# HWProgUSB.net
KiCad netlist of a schematic drawn in EAGLE
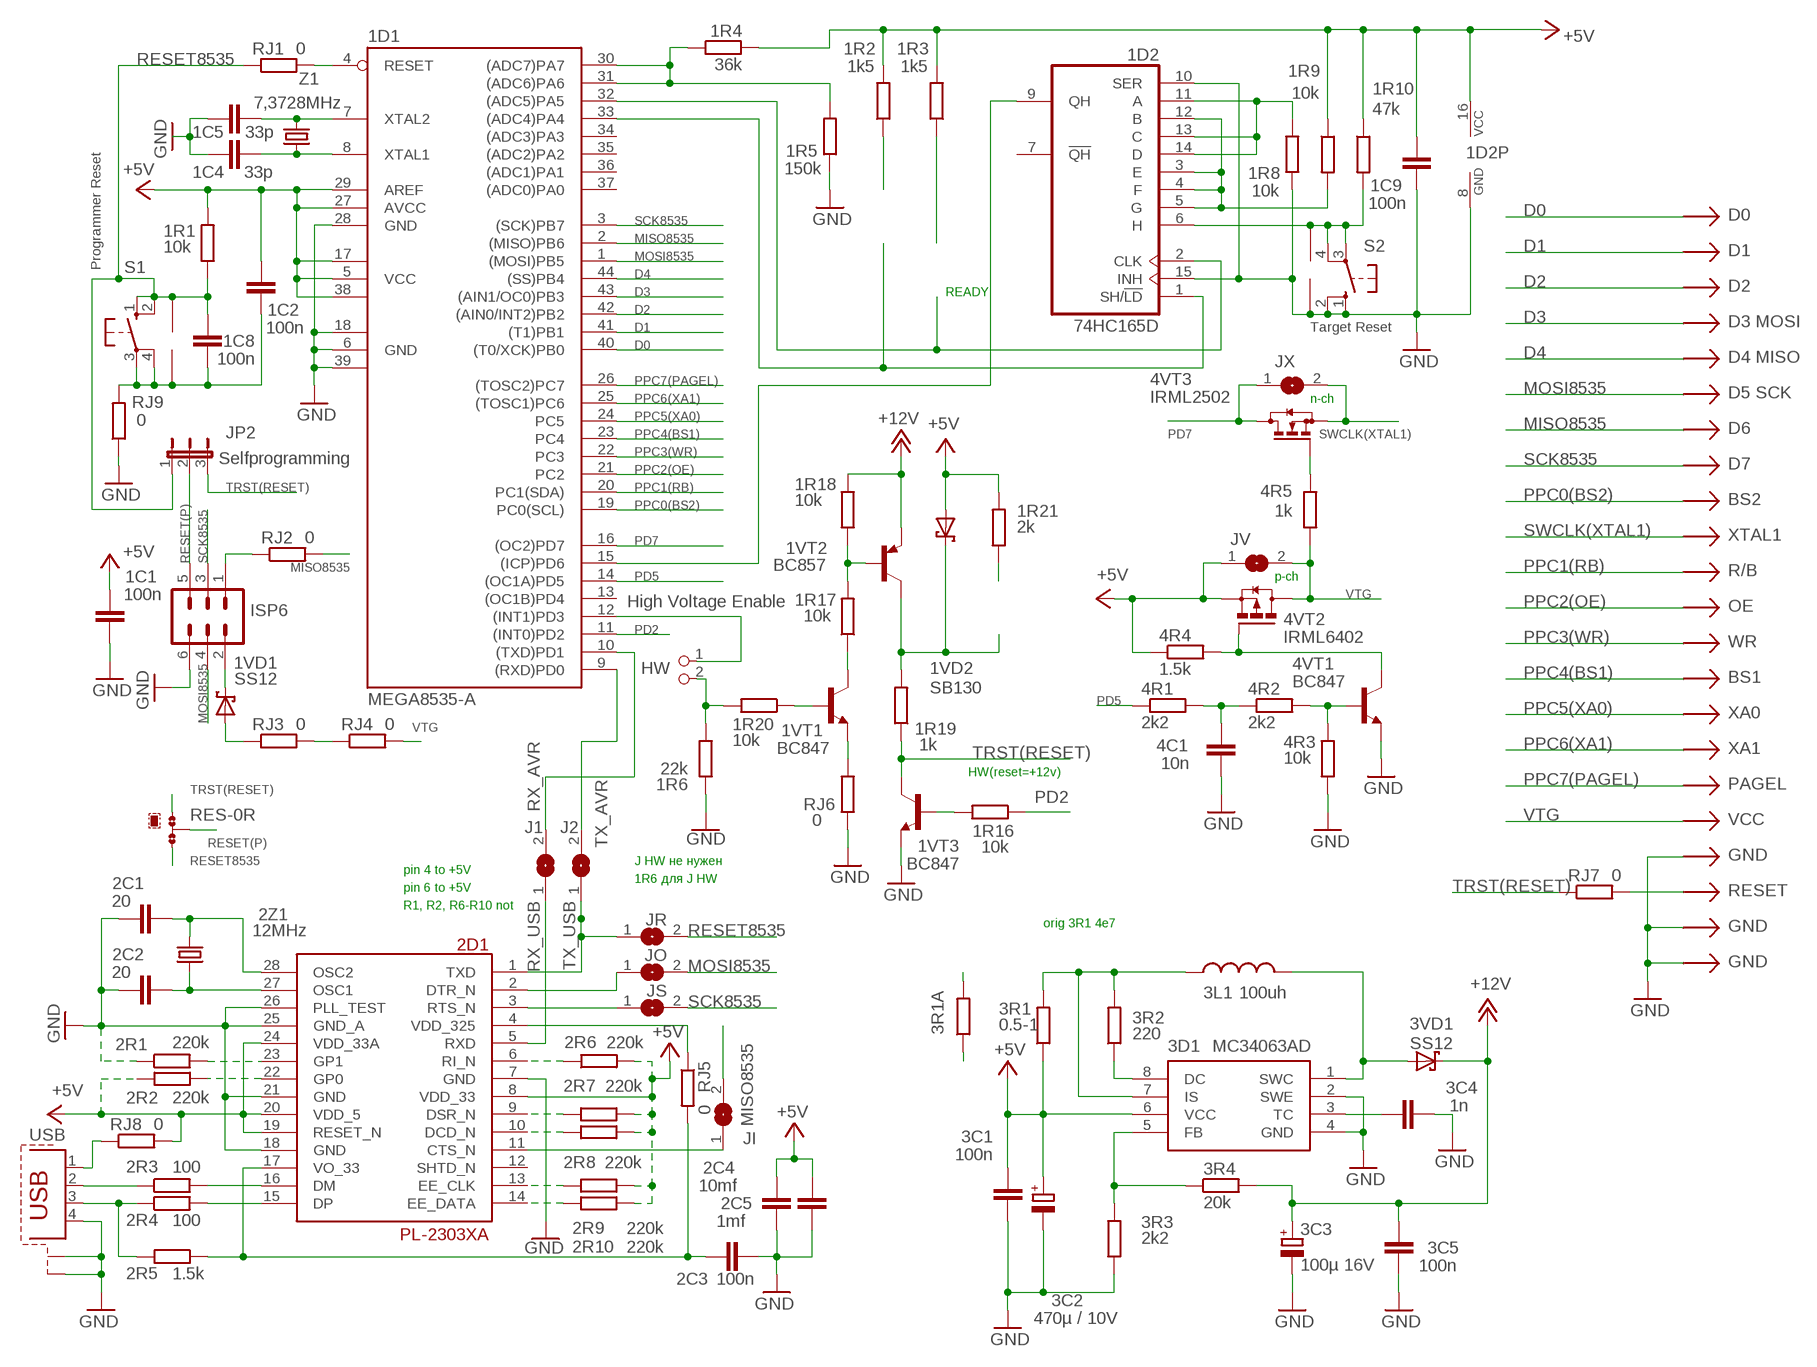
[diagram p0: schematic, sheet 1]

(export (version "E")
  (design (tool "Eeschema 10.0.6"))
  (components
    (comp (ref "1C1")
      (value "100n")
      (footprint "eagle-import:C0805")
      (libsource (lib "eagle-import") (part "rcl_C-EUC0805"))
    )
    (comp (ref "1C2")
      (value "100n")
      (footprint "eagle-import:C0805")
      (libsource (lib "eagle-import") (part "rcl_C-EUC0805"))
    )
    (comp (ref "1C4")
      (value "33p")
      (footprint "eagle-import:C0805")
      (libsource (lib "eagle-import") (part "rcl_C-EUC0805"))
    )
    (comp (ref "1C5")
      (value "33p")
      (footprint "eagle-import:C0805")
      (libsource (lib "eagle-import") (part "rcl_C-EUC0805"))
    )
    (comp (ref "1C8")
      (value "100n")
      (footprint "eagle-import:C0805")
      (libsource (lib "eagle-import") (part "rcl_C-EUC0805"))
    )
    (comp (ref "1C9")
      (value "100n")
      (footprint "eagle-import:C0805")
      (libsource (lib "eagle-import") (part "rcl_C-EUC0805"))
    )
    (comp (ref "1D1")
      (value "MEGA8535-A")
      (footprint "eagle-import:TQFP44")
      (fields (field (name "MPN") "ATMEGA8535-16AU"))
      (libsource (lib "eagle-import") (part "MEGA8535-A"))
    )
    (comp (ref "1D2")
      (value "74HC165D")
      (footprint "eagle-import:SO16")
      (libsource (lib "eagle-import") (part "74165DHC"))
    )
    (comp (ref "1R1")
      (value "10k")
      (footprint "eagle-import:M0805")
      (libsource (lib "eagle-import") (part "R-EU_M0805"))
    )
    (comp (ref "1R2")
      (value "1k5")
      (footprint "eagle-import:M0805")
      (libsource (lib "eagle-import") (part "R-EU_M0805"))
    )
    (comp (ref "1R3")
      (value "1k5")
      (footprint "eagle-import:M0805")
      (libsource (lib "eagle-import") (part "R-EU_M0805"))
    )
    (comp (ref "1R4")
      (value "36k")
      (footprint "eagle-import:M0805")
      (libsource (lib "eagle-import") (part "R-EU_M0805"))
    )
    (comp (ref "1R5")
      (value "150k")
      (footprint "eagle-import:R1206")
      (libsource (lib "eagle-import") (part "R-EU_R1206"))
    )
    (comp (ref "1R6")
      (value "22k")
      (footprint "eagle-import:M1206")
      (libsource (lib "eagle-import") (part "R-EU_M1206"))
    )
    (comp (ref "1R8")
      (value "10k")
      (footprint "eagle-import:M0805")
      (libsource (lib "eagle-import") (part "R-EU_M0805"))
    )
    (comp (ref "1R9")
      (value "10k")
      (footprint "eagle-import:M0805")
      (libsource (lib "eagle-import") (part "R-EU_M0805"))
    )
    (comp (ref "1R10")
      (value "47k")
      (footprint "eagle-import:M0805")
      (libsource (lib "eagle-import") (part "R-EU_M0805"))
    )
    (comp (ref "1R16")
      (value "10k")
      (footprint "eagle-import:R0805")
      (libsource (lib "eagle-import") (part "R-EU_R0805"))
    )
    (comp (ref "1R17")
      (value "10k")
      (footprint "eagle-import:M0805")
      (libsource (lib "eagle-import") (part "R-EU_M0805"))
    )
    (comp (ref "1R18")
      (value "10k")
      (footprint "eagle-import:M0805")
      (libsource (lib "eagle-import") (part "R-EU_M0805"))
    )
    (comp (ref "1R19")
      (value "1k")
      (footprint "eagle-import:M0805")
      (libsource (lib "eagle-import") (part "R-EU_M0805"))
    )
    (comp (ref "1R20")
      (value "10k")
      (footprint "eagle-import:M0805")
      (libsource (lib "eagle-import") (part "R-EU_M0805"))
    )
    (comp (ref "1R21")
      (value "2k")
      (footprint "eagle-import:R1206W")
      (libsource (lib "eagle-import") (part "R-EU_R1206W"))
    )
    (comp (ref "1VD1")
      (value "SS12")
      (footprint "eagle-import:SMB")
      (libsource (lib "eagle-import") (part "SCHOTTKY-DIODESMD"))
    )
    (comp (ref "1VD2")
      (value "SB130")
      (footprint "eagle-import:SMB")
      (libsource (lib "eagle-import") (part "SCHOTTKY-DIODESMD"))
    )
    (comp (ref "1VT1")
      (value "BC847")
      (footprint "eagle-import:SOT23")
      (libsource (lib "eagle-import") (part "BC847"))
    )
    (comp (ref "1VT2")
      (value "BC857")
      (footprint "eagle-import:SOT23-BEC")
      (libsource (lib "eagle-import") (part "-PNP-SOT23-BECBC857A"))
    )
    (comp (ref "1VT3")
      (value "BC847")
      (footprint "eagle-import:SOT23")
      (libsource (lib "eagle-import") (part "BC847"))
    )
    (comp (ref "2C1")
      (value "20")
      (footprint "eagle-import:C0805")
      (libsource (lib "eagle-import") (part "resistor_C-EUC0805"))
    )
    (comp (ref "2C2")
      (value "20")
      (footprint "eagle-import:C0805")
      (libsource (lib "eagle-import") (part "resistor_C-EUC0805"))
    )
    (comp (ref "2C3")
      (value "100n")
      (footprint "eagle-import:C0805")
      (libsource (lib "eagle-import") (part "resistor_C-EUC0805"))
    )
    (comp (ref "2C4")
      (value "10mf")
      (footprint "eagle-import:C1210")
      (libsource (lib "eagle-import") (part "rcl_C-EUC1210"))
    )
    (comp (ref "2C5")
      (value "1mf")
      (footprint "eagle-import:C0805")
      (libsource (lib "eagle-import") (part "rcl_C-EUC0805"))
    )
    (comp (ref "2D1")
      (value "PL-2303XA")
      (footprint "eagle-import:SSOP28DB")
      (libsource (lib "eagle-import") (part "PL-2303XA"))
    )
    (comp (ref "2R1")
      (value "220k")
      (footprint "eagle-import:R0603")
      (libsource (lib "eagle-import") (part "resistor_R-EU_R0603"))
    )
    (comp (ref "2R2")
      (value "220k")
      (footprint "eagle-import:R1206W")
      (libsource (lib "eagle-import") (part "resistor_R-EU_R1206W"))
    )
    (comp (ref "2R3")
      (value "100")
      (footprint "eagle-import:R0603")
      (libsource (lib "eagle-import") (part "resistor_R-EU_R0603"))
    )
    (comp (ref "2R4")
      (value "100")
      (footprint "eagle-import:R0603")
      (libsource (lib "eagle-import") (part "resistor_R-EU_R0603"))
    )
    (comp (ref "2R5")
      (value "1.5k")
      (footprint "eagle-import:R0603")
      (libsource (lib "eagle-import") (part "resistor_R-EU_R0603"))
    )
    (comp (ref "2R6")
      (value "220k")
      (footprint "eagle-import:R1206W")
      (libsource (lib "eagle-import") (part "resistor_R-EU_R1206W"))
    )
    (comp (ref "2R7")
      (value "220k")
      (footprint "eagle-import:R0603")
      (libsource (lib "eagle-import") (part "resistor_R-EU_R0603"))
    )
    (comp (ref "2R8")
      (value "220k")
      (footprint "eagle-import:R0603")
      (libsource (lib "eagle-import") (part "resistor_R-EU_R0603"))
    )
    (comp (ref "2R9")
      (value "220k")
      (footprint "eagle-import:R0603")
      (libsource (lib "eagle-import") (part "resistor_R-EU_R0603"))
    )
    (comp (ref "2R10")
      (value "220k")
      (footprint "eagle-import:R0603")
      (libsource (lib "eagle-import") (part "resistor_R-EU_R0603"))
    )
    (comp (ref "2Z1")
      (value "12MHz")
      (footprint "eagle-import:HC49_S")
      (libsource (lib "eagle-import") (part "CRYSTALHC49S"))
    )
    (comp (ref "3C1")
      (value "100n")
      (footprint "eagle-import:C025-024X044")
      (libsource (lib "eagle-import") (part "C-EU025-024X044"))
    )
    (comp (ref "3C2")
      (value "470µ / 10V")
      (footprint "eagle-import:RCL_E3,5-8")
      (libsource (lib "eagle-import") (part "RCL_CPOL-EUE3.5-8"))
    )
    (comp (ref "3C3")
      (value "100µ 16V")
      (footprint "eagle-import:RCL_E3,5-8")
      (libsource (lib "eagle-import") (part "RCL_CPOL-EUE3.5-8"))
    )
    (comp (ref "3C4")
      (value "1n")
      (footprint "eagle-import:C025-025X050")
      (libsource (lib "eagle-import") (part "rcl_C-EU025-025X050"))
    )
    (comp (ref "3C5")
      (value "100n")
      (footprint "eagle-import:C025-025X050")
      (libsource (lib "eagle-import") (part "rcl_C-EU025-025X050"))
    )
    (comp (ref "3D1")
      (value "MC34063AD")
      (footprint "eagle-import:SOIC8")
      (libsource (lib "eagle-import") (part "MC34063AD"))
    )
    (comp (ref "3L1")
      (value "100uh")
      (footprint "eagle-import:0207_10")
      (libsource (lib "eagle-import") (part "L-US0207/10"))
    )
    (comp (ref "3R1")
      (value "0.5-1")
      (footprint "eagle-import:0204_7")
      (libsource (lib "eagle-import") (part "R-EU_0204/7"))
    )
    (comp (ref "3R1A")
      (value "R-EU_0204/7")
      (footprint "eagle-import:0204_7")
      (libsource (lib "eagle-import") (part "R-EU_0204/7"))
    )
    (comp (ref "3R2")
      (value "220")
      (footprint "eagle-import:0204_7")
      (libsource (lib "eagle-import") (part "R-EU_0204/7"))
    )
    (comp (ref "3R3")
      (value "2k2")
      (footprint "eagle-import:M0805")
      (libsource (lib "eagle-import") (part "R-EU_M0805"))
    )
    (comp (ref "3R4")
      (value "20k")
      (footprint "eagle-import:M0805")
      (libsource (lib "eagle-import") (part "R-EU_M0805"))
    )
    (comp (ref "3VD1")
      (value "SS12")
      (footprint "eagle-import:SMB")
      (libsource (lib "eagle-import") (part "SCHOTTKY-DIODESMD"))
    )
    (comp (ref "4C1")
      (value "10n")
      (footprint "eagle-import:C1206")
      (libsource (lib "eagle-import") (part "rcl_C-EUC1206"))
    )
    (comp (ref "4R1")
      (value "2k2")
      (footprint "eagle-import:M0805")
      (libsource (lib "eagle-import") (part "R-EU_M0805"))
    )
    (comp (ref "4R2")
      (value "2k2")
      (footprint "eagle-import:M1206")
      (libsource (lib "eagle-import") (part "R-EU_M1206"))
    )
    (comp (ref "4R3")
      (value "10k")
      (footprint "eagle-import:M0805")
      (libsource (lib "eagle-import") (part "R-EU_M0805"))
    )
    (comp (ref "4R4")
      (value "1.5k")
      (footprint "eagle-import:M0805")
      (libsource (lib "eagle-import") (part "R-EU_M0805"))
    )
    (comp (ref "4R5")
      (value "1k")
      (footprint "eagle-import:M0805")
      (libsource (lib "eagle-import") (part "R-EU_M0805"))
    )
    (comp (ref "4VT1")
      (value "BC847")
      (footprint "eagle-import:SOT23")
      (libsource (lib "eagle-import") (part "transistor-neu-to92_BC847"))
    )
    (comp (ref "4VT2")
      (value "IRML6402")
      (footprint "eagle-import:SUPER-SOT3")
      (libsource (lib "eagle-import") (part "FDN360P"))
    )
    (comp (ref "4VT3")
      (value "IRML2502")
      (footprint "eagle-import:SOT23")
      (libsource (lib "eagle-import") (part "BSS123"))
    )
    (comp (ref "HW")
      (value "High Voltage Enable")
      (footprint "eagle-import:PINHEAD_1X02")
      (libsource (lib "eagle-import") (part "PINHEAD_PINHD-1X2"))
    )
    (comp (ref "ISP6")
      (value "MA03-2")
      (footprint "eagle-import:MA03-2")
      (libsource (lib "eagle-import") (part "MA03-2"))
    )
    (comp (ref "J1") (value "SJ") (footprint "eagle-import:SJ") (libsource (lib "eagle-import") (part "SJ")))
    (comp (ref "J2") (value "SJ") (footprint "eagle-import:SJ") (libsource (lib "eagle-import") (part "SJ")))
    (comp (ref "JI") (value "SJ") (footprint "eagle-import:SJ") (libsource (lib "eagle-import") (part "SJ")))
    (comp (ref "JO") (value "SJ") (footprint "eagle-import:SJ") (libsource (lib "eagle-import") (part "SJ")))
    (comp (ref "JP2")
      (value "Selfprogramming")
      (footprint "eagle-import:JUMPER_JP2")
      (libsource (lib "eagle-import") (part "JUMPER_JP2E"))
    )
    (comp (ref "JR") (value "SJ") (footprint "eagle-import:SJ") (libsource (lib "eagle-import") (part "SJ")))
    (comp (ref "JS") (value "SJ") (footprint "eagle-import:SJ") (libsource (lib "eagle-import") (part "SJ")))
    (comp (ref "JV") (value "SJ") (footprint "eagle-import:SJ") (libsource (lib "eagle-import") (part "SJ")))
    (comp (ref "JX") (value "SJ") (footprint "eagle-import:SJ") (libsource (lib "eagle-import") (part "SJ")))
    (comp (ref "RES")
      (value "0R-JUMPA")
      (footprint "eagle-import:A0R-JMP")
      (libsource (lib "eagle-import") (part "0R-JUMPA"))
    )
    (comp (ref "RJ1")
      (value "0")
      (footprint "eagle-import:R1206")
      (libsource (lib "eagle-import") (part "R-EU_R1206"))
    )
    (comp (ref "RJ2")
      (value "0")
      (footprint "eagle-import:R1206")
      (libsource (lib "eagle-import") (part "R-EU_R1206"))
    )
    (comp (ref "RJ3")
      (value "0")
      (footprint "eagle-import:R1206")
      (libsource (lib "eagle-import") (part "R-EU_R1206"))
    )
    (comp (ref "RJ4")
      (value "0")
      (footprint "eagle-import:R1206")
      (libsource (lib "eagle-import") (part "R-EU_R1206"))
    )
    (comp (ref "RJ5")
      (value "0")
      (footprint "eagle-import:R1206")
      (libsource (lib "eagle-import") (part "R-EU_R1206"))
    )
    (comp (ref "RJ6")
      (value "0")
      (footprint "eagle-import:R1206")
      (libsource (lib "eagle-import") (part "R-EU_R1206"))
    )
    (comp (ref "RJ7")
      (value "0")
      (footprint "eagle-import:R1206")
      (libsource (lib "eagle-import") (part "R-EU_R1206"))
    )
    (comp (ref "RJ8")
      (value "0")
      (footprint "eagle-import:R1206")
      (libsource (lib "eagle-import") (part "R-EU_R1206"))
    )
    (comp (ref "RJ9")
      (value "0")
      (footprint "eagle-import:R1206")
      (libsource (lib "eagle-import") (part "R-EU_R1206"))
    )
    (comp (ref "S1")
      (value "10-XX")
      (footprint "eagle-import:B3F-10XX")
      (libsource (lib "eagle-import") (part "10-XX"))
    )
    (comp (ref "S2")
      (value "10-XX")
      (footprint "eagle-import:B3F-10XX")
      (libsource (lib "eagle-import") (part "10-XX"))
    )
    (comp (ref "U$1")
      (value "5.08")
      (footprint "eagle-import:KEY")
      (libsource (lib "eagle-import") (part "5.08"))
    )
    (comp (ref "U$2")
      (value "5.08")
      (footprint "eagle-import:KEY")
      (libsource (lib "eagle-import") (part "5.08"))
    )
    (comp (ref "USB")
      (value "PROGRAMMER_PN61729-S")
      (footprint "eagle-import:PROGRAMMER_PN61729-S")
      (libsource (lib "eagle-import") (part "PROGRAMMER_PN61729-S"))
    )
    (comp (ref "X2")
      (value "P_AVR_P")
      (footprint "eagle-import:P_AVR")
      (libsource (lib "eagle-import") (part "P_AVR_P"))
    )
    (comp (ref "Z1")
      (value "7,3728MHz")
      (footprint "eagle-import:HC49U-V")
      (libsource (lib "eagle-import") (part "CRYTALHC49U-V"))
    )
  )
  (nets
    (net (code "1") (name "+5V") (class "Default")
      (node (ref "1C1") (pin "2") (pinfunction "2_2") (pintype "passive"))
      (node (ref "1C2") (pin "2") (pinfunction "2_2") (pintype "passive"))
      (node (ref "1C9") (pin "1") (pinfunction "1_1") (pintype "passive"))
      (node (ref "1D1") (pin "17") (pinfunction "VCC1_17") (pintype "power_in"))
      (node (ref "1D1") (pin "27") (pinfunction "AVCC_27") (pintype "power_in"))
      (node (ref "1D1") (pin "29") (pinfunction "AREF_29") (pintype "passive"))
      (node (ref "1D1") (pin "38") (pinfunction "VCC2_38") (pintype "power_in"))
      (node (ref "1D1") (pin "5") (pinfunction "VCC_5") (pintype "power_in"))
      (node (ref "1D2") (pin "16") (pinfunction "VCC_16") (pintype "power_in"))
      (node (ref "1R1") (pin "2") (pinfunction "2_2") (pintype "passive"))
      (node (ref "1R10") (pin "1") (pinfunction "1_1") (pintype "passive"))
      (node (ref "1R2") (pin "2") (pinfunction "2_2") (pintype "passive"))
      (node (ref "1R21") (pin "2") (pinfunction "2_2") (pintype "passive"))
      (node (ref "1R3") (pin "2") (pinfunction "2_2") (pintype "passive"))
      (node (ref "1R4") (pin "2") (pinfunction "2_2") (pintype "passive"))
      (node (ref "1R9") (pin "1") (pinfunction "1_1") (pintype "passive"))
      (node (ref "1VD2") (pin "A") (pinfunction "A_A") (pintype "passive"))
      (node (ref "2C4") (pin "2") (pinfunction "2_2") (pintype "passive"))
      (node (ref "2C5") (pin "2") (pinfunction "2_2") (pintype "passive"))
      (node (ref "2D1") (pin "19") (pinfunction "RESET_N_19") (pintype "bidirectional"))
      (node (ref "2D1") (pin "20") (pinfunction "VDD_5_20") (pintype "bidirectional"))
      (node (ref "2D1") (pin "24") (pinfunction "VDD_33A_24") (pintype "bidirectional"))
      (node (ref "2D1") (pin "8") (pinfunction "VDD_33_8") (pintype "bidirectional"))
      (node (ref "2R10") (pin "1") (pinfunction "1_1") (pintype "passive"))
      (node (ref "2R2") (pin "1") (pinfunction "1_1") (pintype "passive"))
      (node (ref "2R6") (pin "2") (pinfunction "2_2") (pintype "passive"))
      (node (ref "2R7") (pin "1") (pinfunction "1_1") (pintype "passive"))
      (node (ref "2R8") (pin "1") (pinfunction "1_1") (pintype "passive"))
      (node (ref "2R9") (pin "1") (pinfunction "1_1") (pintype "passive"))
      (node (ref "3C1") (pin "1") (pinfunction "1_1") (pintype "passive"))
      (node (ref "3C2") (pin "+") (pinfunction "+_+") (pintype "passive"))
      (node (ref "3D1") (pin "6") (pinfunction "VCC_6") (pintype "passive"))
      (node (ref "3R1") (pin "1") (pinfunction "1_1") (pintype "passive"))
      (node (ref "3R1A") (pin "1") (pinfunction "1_1") (pintype "passive"))
      (node (ref "4R4") (pin "1") (pinfunction "1_1") (pintype "passive"))
      (node (ref "4VT2") (pin "2") (pinfunction "S_2") (pintype "passive"))
      (node (ref "JV") (pin "1") (pinfunction "1_1") (pintype "passive"))
      (node (ref "RJ8") (pin "2") (pinfunction "2_2") (pintype "passive"))
    )
    (net (code "2") (name "+12V") (class "Default")
      (node (ref "1R18") (pin "2") (pinfunction "2_2") (pintype "passive"))
      (node (ref "1VT2") (pin "E") (pinfunction "E_E") (pintype "passive"))
      (node (ref "3C3") (pin "+") (pinfunction "+_+") (pintype "passive"))
      (node (ref "3C5") (pin "2") (pinfunction "2_2") (pintype "passive"))
      (node (ref "3R4") (pin "2") (pinfunction "2_2") (pintype "passive"))
      (node (ref "3VD1") (pin "C") (pinfunction "C_C") (pintype "passive"))
    )
    (net (code "3") (name "/D0") (class "Default")
      (node (ref "1D1") (pin "40") (pinfunction "(T0/XCK)PB0_40") (pintype "bidirectional"))
      (node (ref "X2") (pin "D0") (pinfunction "D0_D0") (pintype "bidirectional"))
    )
    (net (code "4") (name "/D1") (class "Default")
      (node (ref "1D1") (pin "41") (pinfunction "(T1)PB1_41") (pintype "bidirectional"))
      (node (ref "X2") (pin "D1") (pinfunction "D1_D1") (pintype "bidirectional"))
    )
    (net (code "5") (name "/D2") (class "Default")
      (node (ref "1D1") (pin "42") (pinfunction "(AIN0/INT2)PB2_42") (pintype "bidirectional"))
      (node (ref "X2") (pin "D2") (pinfunction "D2_D2") (pintype "bidirectional"))
    )
    (net (code "6") (name "/D3") (class "Default")
      (node (ref "1D1") (pin "43") (pinfunction "(AIN1/OC0)PB3_43") (pintype "bidirectional"))
      (node (ref "X2") (pin "D3") (pinfunction "D3_D3") (pintype "bidirectional"))
    )
    (net (code "7") (name "/D4") (class "Default")
      (node (ref "1D1") (pin "44") (pinfunction "(SS)PB4_44") (pintype "bidirectional"))
      (node (ref "X2") (pin "D4") (pinfunction "D4_D4") (pintype "bidirectional"))
    )
    (net (code "8") (name "/MISO8535") (class "Default")
      (node (ref "1D1") (pin "2") (pinfunction "(MISO)PB6_2") (pintype "bidirectional"))
      (node (ref "JI") (pin "2") (pinfunction "2_2") (pintype "passive"))
      (node (ref "RJ2") (pin "2") (pinfunction "2_2") (pintype "passive"))
      (node (ref "X2") (pin "D6") (pinfunction "D6_D6") (pintype "bidirectional"))
    )
    (net (code "9") (name "/MOSI8535") (class "Default")
      (node (ref "1D1") (pin "1") (pinfunction "(MOSI)PB5_1") (pintype "bidirectional"))
      (node (ref "ISP6") (pin "4") (pinfunction "4_4") (pintype "passive"))
      (node (ref "JO") (pin "2") (pinfunction "2_2") (pintype "passive"))
      (node (ref "X2") (pin "D5") (pinfunction "D5_D5") (pintype "bidirectional"))
    )
    (net (code "10") (name "/N$105") (class "Default")
      (node (ref "3D1") (pin "7") (pinfunction "IS_7") (pintype "passive"))
      (node (ref "3L1") (pin "1") (pinfunction "1_1") (pintype "passive"))
      (node (ref "3R1") (pin "2") (pinfunction "2_2") (pintype "passive"))
      (node (ref "3R1A") (pin "2") (pinfunction "2_2") (pintype "passive"))
      (node (ref "3R2") (pin "2") (pinfunction "2_2") (pintype "passive"))
    )
    (net (code "11") (name "/PD2") (class "Default")
      (node (ref "1D1") (pin "11") (pinfunction "(INT0)PD2_11") (pintype "bidirectional"))
      (node (ref "1R16") (pin "1") (pinfunction "1_1") (pintype "passive"))
    )
    (net (code "12") (name "/PD5") (class "Default")
      (node (ref "1D1") (pin "14") (pinfunction "(OC1A)PD5_14") (pintype "bidirectional"))
      (node (ref "4R1") (pin "1") (pinfunction "1_1") (pintype "passive"))
    )
    (net (code "13") (name "/PD7") (class "Default")
      (node (ref "1D1") (pin "16") (pinfunction "(OC2)PD7_16") (pintype "bidirectional"))
      (node (ref "4VT3") (pin "3") (pinfunction "D_3") (pintype "passive"))
      (node (ref "JX") (pin "1") (pinfunction "1_1") (pintype "passive"))
    )
    (net (code "14") (name "/PPC0(BS2)") (class "Default")
      (node (ref "1D1") (pin "19") (pinfunction "PC0(SCL)_19") (pintype "bidirectional"))
      (node (ref "X2") (pin "BS2") (pinfunction "BS2_BS2") (pintype "bidirectional"))
    )
    (net (code "15") (name "/PPC1(RB)") (class "Default")
      (node (ref "1D1") (pin "20") (pinfunction "PC1(SDA)_20") (pintype "bidirectional"))
      (node (ref "X2") (pin "RB") (pinfunction "RB_RB") (pintype "bidirectional"))
    )
    (net (code "16") (name "/PPC2(OE)") (class "Default")
      (node (ref "1D1") (pin "21") (pinfunction "PC2_21") (pintype "bidirectional"))
      (node (ref "X2") (pin "OE") (pinfunction "OE_OE") (pintype "bidirectional"))
    )
    (net (code "17") (name "/PPC3(WR)") (class "Default")
      (node (ref "1D1") (pin "22") (pinfunction "PC3_22") (pintype "bidirectional"))
      (node (ref "X2") (pin "WR") (pinfunction "WR_WR") (pintype "bidirectional"))
    )
    (net (code "18") (name "/PPC4(BS1)") (class "Default")
      (node (ref "1D1") (pin "23") (pinfunction "PC4_23") (pintype "bidirectional"))
      (node (ref "X2") (pin "BS1") (pinfunction "BS1_BS1") (pintype "bidirectional"))
    )
    (net (code "19") (name "/PPC5(XA0)") (class "Default")
      (node (ref "1D1") (pin "24") (pinfunction "PC5_24") (pintype "bidirectional"))
      (node (ref "X2") (pin "XA0") (pinfunction "XA0_XA0") (pintype "bidirectional"))
    )
    (net (code "20") (name "/PPC6(XA1)") (class "Default")
      (node (ref "1D1") (pin "25") (pinfunction "(TOSC1)PC6_25") (pintype "bidirectional"))
      (node (ref "X2") (pin "XA1") (pinfunction "XA1_XA1") (pintype "bidirectional"))
    )
    (net (code "21") (name "/PPC7(PAGEL)") (class "Default")
      (node (ref "1D1") (pin "26") (pinfunction "(TOSC2)PC7_26") (pintype "bidirectional"))
      (node (ref "X2") (pin "PAGEL") (pinfunction "PAGEL_PAGEL") (pintype "bidirectional"))
    )
    (net (code "22") (name "/RESET(P)") (class "Default")
      (node (ref "ISP6") (pin "5") (pinfunction "5_5") (pintype "passive"))
      (node (ref "JP2") (pin "2") (pinfunction "2_2") (pintype "passive"))
      (node (ref "RES") (pin "2") (pinfunction "2_2") (pintype "passive"))
    )
    (net (code "23") (name "/RESET8535") (class "Default")
      (node (ref "1C8") (pin "2") (pinfunction "2_2") (pintype "passive"))
      (node (ref "1R1") (pin "1") (pinfunction "1_1") (pintype "passive"))
      (node (ref "JP2") (pin "1") (pinfunction "1_1") (pintype "passive"))
      (node (ref "JR") (pin "2") (pinfunction "2_2") (pintype "passive"))
      (node (ref "RES") (pin "3") (pinfunction "3_3") (pintype "passive"))
      (node (ref "RJ1") (pin "1") (pinfunction "1_1") (pintype "passive"))
      (node (ref "S1") (pin "1") (pinfunction "S_1") (pintype "passive"))
      (node (ref "S1") (pin "2") (pinfunction "S1_2") (pintype "passive"))
      (node (ref "U$1") (pin "P$2") (pinfunction "P$2_P$2") (pintype "bidirectional"))
    )
    (net (code "24") (name "/RX_AVR") (class "Default")
      (node (ref "1D1") (pin "10") (pinfunction "(TXD)PD1_10") (pintype "bidirectional"))
      (node (ref "J1") (pin "2") (pinfunction "2_2") (pintype "passive"))
    )
    (net (code "25") (name "/RX_USB") (class "Default")
      (node (ref "2D1") (pin "5") (pinfunction "RXD_5") (pintype "bidirectional"))
      (node (ref "J1") (pin "1") (pinfunction "1_1") (pintype "passive"))
    )
    (net (code "26") (name "/SCK8535") (class "Default")
      (node (ref "1D1") (pin "3") (pinfunction "(SCK)PB7_3") (pintype "bidirectional"))
      (node (ref "ISP6") (pin "3") (pinfunction "3_3") (pintype "passive"))
      (node (ref "JS") (pin "2") (pinfunction "2_2") (pintype "passive"))
      (node (ref "X2") (pin "D7") (pinfunction "D7_D7") (pintype "bidirectional"))
    )
    (net (code "27") (name "/SWCLK(XTAL1)") (class "Default")
      (node (ref "4VT3") (pin "2") (pinfunction "S_2") (pintype "passive"))
      (node (ref "JX") (pin "2") (pinfunction "2_2") (pintype "passive"))
      (node (ref "X2") (pin "XTAL1") (pinfunction "XTAL1_XTAL1") (pintype "bidirectional"))
    )
    (net (code "28") (name "/TRST(RESET)") (class "Default")
      (node (ref "1R19") (pin "1") (pinfunction "1_1") (pintype "passive"))
      (node (ref "1VT3") (pin "3") (pinfunction "C_3") (pintype "passive"))
      (node (ref "JP2") (pin "3") (pinfunction "3_3") (pintype "passive"))
      (node (ref "RES") (pin "1") (pinfunction "1_1") (pintype "passive"))
      (node (ref "RJ7") (pin "1") (pinfunction "1_1") (pintype "passive"))
    )
    (net (code "29") (name "/TX_AVR") (class "Default")
      (node (ref "1D1") (pin "9") (pinfunction "(RXD)PD0_9") (pintype "bidirectional"))
      (node (ref "J2") (pin "2") (pinfunction "2_2") (pintype "passive"))
    )
    (net (code "30") (name "/TX_USB") (class "Default")
      (node (ref "2D1") (pin "1") (pinfunction "TXD_1") (pintype "bidirectional"))
      (node (ref "J2") (pin "1") (pinfunction "1_1") (pintype "passive"))
      (node (ref "JR") (pin "1") (pinfunction "1_1") (pintype "passive"))
    )
    (net (code "31") (name "/VTG") (class "Default")
      (node (ref "4R5") (pin "1") (pinfunction "1_1") (pintype "passive"))
      (node (ref "4VT2") (pin "3") (pinfunction "D_3") (pintype "passive"))
      (node (ref "JV") (pin "2") (pinfunction "2_2") (pintype "passive"))
      (node (ref "RJ4") (pin "2") (pinfunction "2_2") (pintype "passive"))
      (node (ref "X2") (pin "VCC") (pinfunction "VCC_VCC") (pintype "bidirectional"))
    )
    (net (code "32") (name "GND") (class "Default")
      (node (ref "1C1") (pin "1") (pinfunction "1_1") (pintype "passive"))
      (node (ref "1C4") (pin "1") (pinfunction "1_1") (pintype "passive"))
      (node (ref "1C5") (pin "1") (pinfunction "1_1") (pintype "passive"))
      (node (ref "1C9") (pin "2") (pinfunction "2_2") (pintype "passive"))
      (node (ref "1D1") (pin "18") (pinfunction "GND1_18") (pintype "power_in"))
      (node (ref "1D1") (pin "28") (pinfunction "GND_28") (pintype "power_in"))
      (node (ref "1D1") (pin "39") (pinfunction "GND2_39") (pintype "power_in"))
      (node (ref "1D1") (pin "6") (pinfunction "GND_6") (pintype "power_in"))
      (node (ref "1D2") (pin "10") (pinfunction "SER_10") (pintype "input"))
      (node (ref "1D2") (pin "15") (pinfunction "INH_15") (pintype "input"))
      (node (ref "1D2") (pin "8") (pinfunction "GND_8") (pintype "power_in"))
      (node (ref "1R5") (pin "1") (pinfunction "1_1") (pintype "passive"))
      (node (ref "1R6") (pin "1") (pinfunction "1_1") (pintype "passive"))
      (node (ref "1R8") (pin "1") (pinfunction "1_1") (pintype "passive"))
      (node (ref "1VT3") (pin "2") (pinfunction "E_2") (pintype "passive"))
      (node (ref "2C1") (pin "1") (pinfunction "1_1") (pintype "passive"))
      (node (ref "2C2") (pin "1") (pinfunction "1_1") (pintype "passive"))
      (node (ref "2C3") (pin "2") (pinfunction "2_2") (pintype "passive"))
      (node (ref "2C4") (pin "1") (pinfunction "1_1") (pintype "passive"))
      (node (ref "2C5") (pin "1") (pinfunction "1_1") (pintype "passive"))
      (node (ref "2D1") (pin "18") (pinfunction "GND_18") (pintype "bidirectional"))
      (node (ref "2D1") (pin "21") (pinfunction "GND_21") (pintype "bidirectional"))
      (node (ref "2D1") (pin "25") (pinfunction "GND_A_25") (pintype "bidirectional"))
      (node (ref "2D1") (pin "26") (pinfunction "PLL_TEST_26") (pintype "bidirectional"))
      (node (ref "2D1") (pin "7") (pinfunction "GND_7") (pintype "bidirectional"))
      (node (ref "2R1") (pin "1") (pinfunction "1_1") (pintype "passive"))
      (node (ref "3C1") (pin "2") (pinfunction "2_2") (pintype "passive"))
      (node (ref "3C2") (pin "-") (pinfunction "-_-") (pintype "passive"))
      (node (ref "3C3") (pin "-") (pinfunction "-_-") (pintype "passive"))
      (node (ref "3C4") (pin "2") (pinfunction "2_2") (pintype "passive"))
      (node (ref "3C5") (pin "1") (pinfunction "1_1") (pintype "passive"))
      (node (ref "3D1") (pin "2") (pinfunction "SWE_2") (pintype "passive"))
      (node (ref "3D1") (pin "4") (pinfunction "GND_4") (pintype "passive"))
      (node (ref "3R3") (pin "1") (pinfunction "1_1") (pintype "passive"))
      (node (ref "4C1") (pin "1") (pinfunction "1_1") (pintype "passive"))
      (node (ref "4R3") (pin "1") (pinfunction "1_1") (pintype "passive"))
      (node (ref "4VT1") (pin "2") (pinfunction "E_2") (pintype "passive"))
      (node (ref "ISP6") (pin "6") (pinfunction "6_6") (pintype "passive"))
      (node (ref "RJ6") (pin "1") (pinfunction "1_1") (pintype "passive"))
      (node (ref "RJ9") (pin "1") (pinfunction "1_1") (pintype "passive"))
      (node (ref "S2") (pin "1") (pinfunction "S_1") (pintype "passive"))
      (node (ref "S2") (pin "2") (pinfunction "S1_2") (pintype "passive"))
      (node (ref "U$2") (pin "P$1") (pinfunction "P$1_P$1") (pintype "bidirectional"))
      (node (ref "USB") (pin "4") (pinfunction "4_4") (pintype "passive"))
      (node (ref "USB") (pin "S1") (pinfunction "S1_S1") (pintype "passive"))
      (node (ref "USB") (pin "S2") (pinfunction "S2_S2") (pintype "passive"))
      (node (ref "X2") (pin "GND") (pinfunction "GND_GND") (pintype "bidirectional"))
      (node (ref "X2") (pin "GND2") (pinfunction "GND2_GND2") (pintype "bidirectional"))
      (node (ref "X2") (pin "P$1") (pinfunction "LGND_P$1") (pintype "bidirectional"))
    )
    (net (code "33") (name "Net-(1D1-(ADC4)PA4)") (class "Default")
      (node (ref "1D1") (pin "33") (pinfunction "(ADC4)PA4_33") (pintype "bidirectional"))
      (node (ref "1D2") (pin "1") (pinfunction "SH/~{LD}_1") (pintype "input"))
    )
    (net (code "34") (name "Net-(1D1-(ADC5)PA5)") (class "Default")
      (node (ref "1D1") (pin "32") (pinfunction "(ADC5)PA5_32") (pintype "bidirectional"))
      (node (ref "1D2") (pin "2") (pinfunction "CLK_2") (pintype "input"))
    )
    (net (code "35") (name "Net-(1D1-(ADC6)PA6)") (class "Default")
      (node (ref "1D1") (pin "30") (pinfunction "(ADC7)PA7_30") (pintype "bidirectional"))
      (node (ref "1D1") (pin "31") (pinfunction "(ADC6)PA6_31") (pintype "bidirectional"))
      (node (ref "1R4") (pin "1") (pinfunction "1_1") (pintype "passive"))
      (node (ref "1R5") (pin "2") (pinfunction "2_2") (pintype "passive"))
    )
    (net (code "36") (name "Net-(1D1-(ICP)PD6)") (class "Default")
      (node (ref "1D1") (pin "15") (pinfunction "(ICP)PD6_15") (pintype "bidirectional"))
      (node (ref "1D2") (pin "9") (pinfunction "QH_9") (pintype "output"))
    )
    (net (code "37") (name "Net-(1D1-(INT1)PD3)") (class "Default")
      (node (ref "1D1") (pin "12") (pinfunction "(INT1)PD3_12") (pintype "bidirectional"))
      (node (ref "HW") (pin "1") (pinfunction "1_1") (pintype "passive"))
    )
    (net (code "38") (name "Net-(1D1-RESET)") (class "Default")
      (node (ref "1D1") (pin "4") (pinfunction "RESET_4") (pintype "input"))
      (node (ref "RJ1") (pin "2") (pinfunction "2_2") (pintype "passive"))
    )
    (net (code "39") (name "Net-(1D1-XTAL1)") (class "Default")
      (node (ref "1C4") (pin "2") (pinfunction "2_2") (pintype "passive"))
      (node (ref "1D1") (pin "8") (pinfunction "XTAL1_8") (pintype "bidirectional"))
      (node (ref "Z1") (pin "1") (pinfunction "1_1") (pintype "passive"))
    )
    (net (code "40") (name "Net-(1D1-XTAL2)") (class "Default")
      (node (ref "1C5") (pin "2") (pinfunction "2_2") (pintype "passive"))
      (node (ref "1D1") (pin "7") (pinfunction "XTAL2_7") (pintype "bidirectional"))
      (node (ref "Z1") (pin "2") (pinfunction "2_2") (pintype "passive"))
    )
    (net (code "41") (name "Net-(1D2A-A)") (class "Default")
      (node (ref "1D2") (pin "11") (pinfunction "A_11") (pintype "input"))
      (node (ref "1D2") (pin "13") (pinfunction "C_13") (pintype "input"))
      (node (ref "1D2") (pin "14") (pinfunction "D_14") (pintype "input"))
      (node (ref "1R8") (pin "2") (pinfunction "2_2") (pintype "passive"))
    )
    (net (code "42") (name "Net-(1D2A-B)") (class "Default")
      (node (ref "1D2") (pin "12") (pinfunction "B_12") (pintype "input"))
      (node (ref "1D2") (pin "3") (pinfunction "E_3") (pintype "input"))
      (node (ref "1D2") (pin "4") (pinfunction "F_4") (pintype "input"))
      (node (ref "1D2") (pin "5") (pinfunction "G_5") (pintype "input"))
      (node (ref "1R9") (pin "2") (pinfunction "2_2") (pintype "passive"))
    )
    (net (code "43") (name "Net-(1D2A-H)") (class "Default")
      (node (ref "1D2") (pin "6") (pinfunction "H_6") (pintype "input"))
      (node (ref "1R10") (pin "2") (pinfunction "2_2") (pintype "passive"))
      (node (ref "S2") (pin "3") (pinfunction "P_3") (pintype "passive"))
      (node (ref "S2") (pin "4") (pinfunction "P1_4") (pintype "passive"))
      (node (ref "U$2") (pin "P$2") (pinfunction "P$2_P$2") (pintype "bidirectional"))
    )
    (net (code "44") (name "Net-(1R17-Pad2)") (class "Default")
      (node (ref "1R17") (pin "2") (pinfunction "2_2") (pintype "passive"))
      (node (ref "1R18") (pin "1") (pinfunction "1_1") (pintype "passive"))
      (node (ref "1VT2") (pin "B") (pinfunction "B_B") (pintype "passive"))
    )
    (net (code "45") (name "Net-(1R19-Pad2)") (class "Default")
      (node (ref "1R19") (pin "2") (pinfunction "2_2") (pintype "passive"))
      (node (ref "1VD2") (pin "C") (pinfunction "C_C") (pintype "passive"))
      (node (ref "1VT2") (pin "C") (pinfunction "C_C") (pintype "passive"))
    )
    (net (code "46") (name "Net-(1R20-Pad2)") (class "Default")
      (node (ref "1R20") (pin "2") (pinfunction "2_2") (pintype "passive"))
      (node (ref "1R6") (pin "2") (pinfunction "2_2") (pintype "passive"))
      (node (ref "HW") (pin "2") (pinfunction "2_2") (pintype "passive"))
    )
    (net (code "47") (name "Net-(1VD1-PadA)") (class "Default")
      (node (ref "1VD1") (pin "A") (pinfunction "A_A") (pintype "passive"))
      (node (ref "RJ3") (pin "1") (pinfunction "1_1") (pintype "passive"))
    )
    (net (code "48") (name "Net-(1VD1-PadC)") (class "Default")
      (node (ref "1VD1") (pin "C") (pinfunction "C_C") (pintype "passive"))
      (node (ref "ISP6") (pin "2") (pinfunction "2_2") (pintype "passive"))
    )
    (net (code "49") (name "Net-(1VT1-B)") (class "Default")
      (node (ref "1R20") (pin "1") (pinfunction "1_1") (pintype "passive"))
      (node (ref "1VT1") (pin "1") (pinfunction "B_1") (pintype "passive"))
    )
    (net (code "50") (name "Net-(1VT1-C)") (class "Default")
      (node (ref "1R17") (pin "1") (pinfunction "1_1") (pintype "passive"))
      (node (ref "1VT1") (pin "3") (pinfunction "C_3") (pintype "passive"))
    )
    (net (code "51") (name "Net-(1VT1-E)") (class "Default")
      (node (ref "1VT1") (pin "2") (pinfunction "E_2") (pintype "passive"))
      (node (ref "RJ6") (pin "2") (pinfunction "2_2") (pintype "passive"))
    )
    (net (code "52") (name "Net-(1VT3-B)") (class "Default")
      (node (ref "1R16") (pin "2") (pinfunction "2_2") (pintype "passive"))
      (node (ref "1VT3") (pin "1") (pinfunction "B_1") (pintype "passive"))
    )
    (net (code "53") (name "Net-(2D1-CTS_N)") (class "Default")
      (node (ref "2D1") (pin "11") (pinfunction "CTS_N_11") (pintype "bidirectional"))
      (node (ref "JI") (pin "1") (pinfunction "1_1") (pintype "passive"))
    )
    (net (code "54") (name "Net-(2D1-DCD_N)") (class "Default")
      (node (ref "2D1") (pin "10") (pinfunction "DCD_N_10") (pintype "bidirectional"))
      (node (ref "2R8") (pin "2") (pinfunction "2_2") (pintype "passive"))
    )
    (net (code "55") (name "Net-(2D1-DM)") (class "Default")
      (node (ref "2D1") (pin "16") (pinfunction "DM_16") (pintype "bidirectional"))
      (node (ref "2R3") (pin "2") (pinfunction "2_2") (pintype "passive"))
    )
    (net (code "56") (name "Net-(2D1-DP)") (class "Default")
      (node (ref "2D1") (pin "15") (pinfunction "DP_15") (pintype "bidirectional"))
      (node (ref "2R4") (pin "2") (pinfunction "2_2") (pintype "passive"))
    )
    (net (code "57") (name "Net-(2D1-DSR_N)") (class "Default")
      (node (ref "2D1") (pin "9") (pinfunction "DSR_N_9") (pintype "bidirectional"))
      (node (ref "2R7") (pin "2") (pinfunction "2_2") (pintype "passive"))
    )
    (net (code "58") (name "Net-(2D1-DTR_N)") (class "Default")
      (node (ref "2D1") (pin "2") (pinfunction "DTR_N_2") (pintype "bidirectional"))
      (node (ref "JO") (pin "1") (pinfunction "1_1") (pintype "passive"))
    )
    (net (code "59") (name "Net-(2D1-EE_CLK)") (class "Default")
      (node (ref "2D1") (pin "13") (pinfunction "EE_CLK_13") (pintype "bidirectional"))
      (node (ref "2R9") (pin "2") (pinfunction "2_2") (pintype "passive"))
    )
    (net (code "60") (name "Net-(2D1-EE_DATA)") (class "Default")
      (node (ref "2D1") (pin "14") (pinfunction "EE_DATA_14") (pintype "bidirectional"))
      (node (ref "2R10") (pin "2") (pinfunction "2_2") (pintype "passive"))
    )
    (net (code "61") (name "Net-(2D1-GP0)") (class "Default")
      (node (ref "2D1") (pin "22") (pinfunction "GP0_22") (pintype "bidirectional"))
      (node (ref "2R2") (pin "2") (pinfunction "2_2") (pintype "passive"))
    )
    (net (code "62") (name "Net-(2D1-GP1)") (class "Default")
      (node (ref "2D1") (pin "23") (pinfunction "GP1_23") (pintype "bidirectional"))
      (node (ref "2R1") (pin "2") (pinfunction "2_2") (pintype "passive"))
    )
    (net (code "63") (name "Net-(2D1-OSC1)") (class "Default")
      (node (ref "2C2") (pin "2") (pinfunction "2_2") (pintype "passive"))
      (node (ref "2D1") (pin "27") (pinfunction "OSC1_27") (pintype "bidirectional"))
      (node (ref "2Z1") (pin "1") (pinfunction "1_1") (pintype "passive"))
    )
    (net (code "64") (name "Net-(2D1-OSC2)") (class "Default")
      (node (ref "2C1") (pin "2") (pinfunction "2_2") (pintype "passive"))
      (node (ref "2D1") (pin "28") (pinfunction "OSC2_28") (pintype "bidirectional"))
      (node (ref "2Z1") (pin "2") (pinfunction "2_2") (pintype "passive"))
    )
    (net (code "65") (name "Net-(2D1-RI_N)") (class "Default")
      (node (ref "2D1") (pin "6") (pinfunction "RI_N_6") (pintype "bidirectional"))
      (node (ref "2R6") (pin "1") (pinfunction "1_1") (pintype "passive"))
    )
    (net (code "66") (name "Net-(2D1-RTS_N)") (class "Default")
      (node (ref "2D1") (pin "3") (pinfunction "RTS_N_3") (pintype "bidirectional"))
      (node (ref "JS") (pin "1") (pinfunction "1_1") (pintype "passive"))
    )
    (net (code "67") (name "Net-(2D1-VDD_325)") (class "Default")
      (node (ref "2D1") (pin "4") (pinfunction "VDD_325_4") (pintype "bidirectional"))
      (node (ref "RJ5") (pin "1") (pinfunction "1_1") (pintype "passive"))
    )
    (net (code "68") (name "Net-(2D1-VO_33)") (class "Default")
      (node (ref "2C3") (pin "1") (pinfunction "1_1") (pintype "passive"))
      (node (ref "2D1") (pin "17") (pinfunction "VO_33_17") (pintype "bidirectional"))
      (node (ref "2R5") (pin "1") (pinfunction "1_1") (pintype "passive"))
      (node (ref "RJ5") (pin "2") (pinfunction "2_2") (pintype "passive"))
    )
    (net (code "69") (name "Net-(2R3-Pad1)") (class "Default")
      (node (ref "2R3") (pin "1") (pinfunction "1_1") (pintype "passive"))
      (node (ref "USB") (pin "2") (pinfunction "2_2") (pintype "passive"))
    )
    (net (code "70") (name "Net-(2R4-Pad1)") (class "Default")
      (node (ref "2R4") (pin "1") (pinfunction "1_1") (pintype "passive"))
      (node (ref "2R5") (pin "2") (pinfunction "2_2") (pintype "passive"))
      (node (ref "USB") (pin "3") (pinfunction "3_3") (pintype "passive"))
    )
    (net (code "71") (name "Net-(3D1-DC)") (class "Default")
      (node (ref "3D1") (pin "8") (pinfunction "DC_8") (pintype "passive"))
      (node (ref "3R2") (pin "1") (pinfunction "1_1") (pintype "passive"))
    )
    (net (code "72") (name "Net-(3D1-FB)") (class "Default")
      (node (ref "3D1") (pin "5") (pinfunction "FB_5") (pintype "passive"))
      (node (ref "3R3") (pin "2") (pinfunction "2_2") (pintype "passive"))
      (node (ref "3R4") (pin "1") (pinfunction "1_1") (pintype "passive"))
    )
    (net (code "73") (name "Net-(3D1-SWC)") (class "Default")
      (node (ref "3D1") (pin "1") (pinfunction "SWC_1") (pintype "passive"))
      (node (ref "3L1") (pin "2") (pinfunction "2_2") (pintype "passive"))
      (node (ref "3VD1") (pin "A") (pinfunction "A_A") (pintype "passive"))
    )
    (net (code "74") (name "Net-(3D1-TC)") (class "Default")
      (node (ref "3C4") (pin "1") (pinfunction "1_1") (pintype "passive"))
      (node (ref "3D1") (pin "3") (pinfunction "TC_3") (pintype "passive"))
    )
    (net (code "75") (name "Net-(4C1-Pad2)") (class "Default")
      (node (ref "4C1") (pin "2") (pinfunction "2_2") (pintype "passive"))
      (node (ref "4R1") (pin "2") (pinfunction "2_2") (pintype "passive"))
      (node (ref "4R2") (pin "1") (pinfunction "1_1") (pintype "passive"))
    )
    (net (code "76") (name "Net-(4VT1-B)") (class "Default")
      (node (ref "4R2") (pin "2") (pinfunction "2_2") (pintype "passive"))
      (node (ref "4R3") (pin "2") (pinfunction "2_2") (pintype "passive"))
      (node (ref "4VT1") (pin "1") (pinfunction "B_1") (pintype "passive"))
    )
    (net (code "77") (name "Net-(4VT1-C)") (class "Default")
      (node (ref "4R4") (pin "2") (pinfunction "2_2") (pintype "passive"))
      (node (ref "4VT1") (pin "3") (pinfunction "C_3") (pintype "passive"))
      (node (ref "4VT2") (pin "1") (pinfunction "G_1") (pintype "passive"))
    )
    (net (code "78") (name "Net-(4VT3-G)") (class "Default")
      (node (ref "4R5") (pin "2") (pinfunction "2_2") (pintype "passive"))
      (node (ref "4VT3") (pin "1") (pinfunction "G_1") (pintype "passive"))
    )
    (net (code "79") (name "Net-(ISP6-Pad1)") (class "Default")
      (node (ref "ISP6") (pin "1") (pinfunction "1_1") (pintype "passive"))
      (node (ref "RJ2") (pin "1") (pinfunction "1_1") (pintype "passive"))
    )
    (net (code "80") (name "Net-(RJ3-Pad2)") (class "Default")
      (node (ref "RJ3") (pin "2") (pinfunction "2_2") (pintype "passive"))
      (node (ref "RJ4") (pin "1") (pinfunction "1_1") (pintype "passive"))
    )
    (net (code "81") (name "Net-(RJ7-Pad2)") (class "Default")
      (node (ref "RJ7") (pin "2") (pinfunction "2_2") (pintype "passive"))
      (node (ref "X2") (pin "RESET") (pinfunction "RESET_RESET") (pintype "bidirectional"))
    )
    (net (code "82") (name "Net-(RJ8-Pad1)") (class "Default")
      (node (ref "RJ8") (pin "1") (pinfunction "1_1") (pintype "passive"))
      (node (ref "USB") (pin "1") (pinfunction "1_1") (pintype "passive"))
    )
    (net (code "83") (name "Net-(S1-P)") (class "Default")
      (node (ref "1C2") (pin "1") (pinfunction "1_1") (pintype "passive"))
      (node (ref "1C8") (pin "1") (pinfunction "1_1") (pintype "passive"))
      (node (ref "RJ9") (pin "2") (pinfunction "2_2") (pintype "passive"))
      (node (ref "S1") (pin "3") (pinfunction "P_3") (pintype "passive"))
      (node (ref "S1") (pin "4") (pinfunction "P1_4") (pintype "passive"))
      (node (ref "U$1") (pin "P$1") (pinfunction "P$1_P$1") (pintype "bidirectional"))
    )
    (net (code "84") (name "unconnected-(1D1-(ADC0)PA0-Pad37)") (class "Default")
      (node (ref "1D1") (pin "37") (pinfunction "(ADC0)PA0_37") (pintype "bidirectional"))
    )
    (net (code "85") (name "unconnected-(1D1-(ADC1)PA1-Pad36)") (class "Default")
      (node (ref "1D1") (pin "36") (pinfunction "(ADC1)PA1_36") (pintype "bidirectional"))
    )
    (net (code "86") (name "unconnected-(1D1-(ADC2)PA2-Pad35)") (class "Default")
      (node (ref "1D1") (pin "35") (pinfunction "(ADC2)PA2_35") (pintype "bidirectional"))
    )
    (net (code "87") (name "unconnected-(1D1-(ADC3)PA3-Pad34)") (class "Default")
      (node (ref "1D1") (pin "34") (pinfunction "(ADC3)PA3_34") (pintype "bidirectional"))
    )
    (net (code "88") (name "unconnected-(1D1-(OC1B)PD4-Pad13)") (class "Default")
      (node (ref "1D1") (pin "13") (pinfunction "(OC1B)PD4_13") (pintype "bidirectional"))
    )
    (net (code "89") (name "unconnected-(1D2A-~{QH}-Pad7)") (class "Default")
      (node (ref "1D2") (pin "7") (pinfunction "~{QH}_7") (pintype "output"))
    )
    (net (code "90") (name "unconnected-(1R2-Pad1)") (class "Default")
      (node (ref "1R2") (pin "1") (pinfunction "1_1") (pintype "passive"))
    )
    (net (code "91") (name "unconnected-(1R3-Pad1)") (class "Default")
      (node (ref "1R3") (pin "1") (pinfunction "1_1") (pintype "passive"))
    )
    (net (code "92") (name "unconnected-(1R21-Pad1)") (class "Default")
      (node (ref "1R21") (pin "1") (pinfunction "1_1") (pintype "passive"))
    )
    (net (code "93") (name "unconnected-(2D1-SHTD_N-Pad12)") (class "Default")
      (node (ref "2D1") (pin "12") (pinfunction "SHTD_N_12") (pintype "bidirectional"))
    )
  )
)
